# LightTable_Borders_CM_SP_ExternalMirror.net
KiCad netlist of a schematic drawn in EAGLE
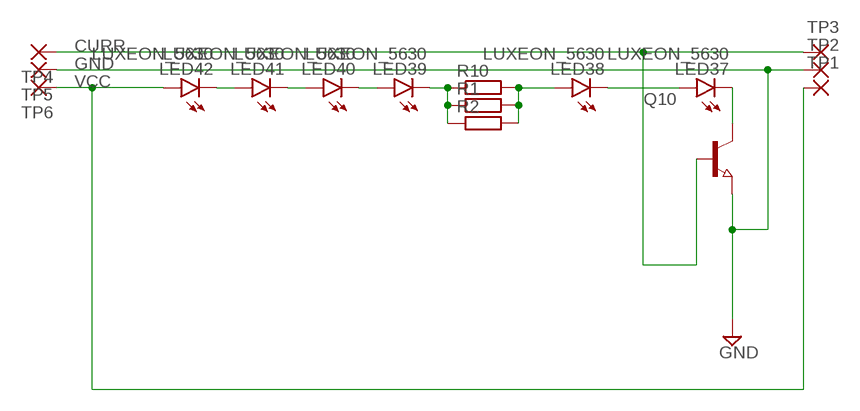
[diagram p0: schematic, sheet 1]

(export (version "E")
  (design (tool "Eeschema 10.0.6"))
  (components
    (comp (ref "LED37")
      (value "LUXEON_5630")
      (footprint "eagle-import:LUXEON_5630")
      (libsource (lib "eagle-import") (part "LUXEON_5630"))
    )
    (comp (ref "LED38")
      (value "LUXEON_5630")
      (footprint "eagle-import:LUXEON_5630")
      (libsource (lib "eagle-import") (part "LUXEON_5630"))
    )
    (comp (ref "LED39")
      (value "LUXEON_5630")
      (footprint "eagle-import:LUXEON_5630")
      (libsource (lib "eagle-import") (part "LUXEON_5630"))
    )
    (comp (ref "LED40")
      (value "LUXEON_5630")
      (footprint "eagle-import:LUXEON_5630")
      (libsource (lib "eagle-import") (part "LUXEON_5630"))
    )
    (comp (ref "LED41")
      (value "LUXEON_5630")
      (footprint "eagle-import:LUXEON_5630")
      (libsource (lib "eagle-import") (part "LUXEON_5630"))
    )
    (comp (ref "LED42")
      (value "LUXEON_5630")
      (footprint "eagle-import:LUXEON_5630")
      (libsource (lib "eagle-import") (part "LUXEON_5630"))
    )
    (comp (ref "Q10")
      (value "NPN-TRANSISTOR_SOT23")
      (footprint "eagle-import:SOT23")
      (libsource (lib "eagle-import") (part "NPN-TRANSISTOR_SOT23"))
    )
    (comp (ref "R1")
      (value "R-EU_R0805")
      (footprint "eagle-import:R0805")
      (libsource (lib "eagle-import") (part "R-EU_R0805"))
    )
    (comp (ref "R2")
      (value "R-EU_R0805")
      (footprint "eagle-import:R0805")
      (libsource (lib "eagle-import") (part "R-EU_R0805"))
    )
    (comp (ref "R10")
      (value "R-EU_R0805")
      (footprint "eagle-import:R0805")
      (libsource (lib "eagle-import") (part "R-EU_R0805"))
    )
    (comp (ref "TP1")
      (value "LSP10")
      (footprint "eagle-import:1,6_0,8")
      (libsource (lib "eagle-import") (part "1,6/0,8"))
    )
    (comp (ref "TP2")
      (value "LSP10")
      (footprint "eagle-import:1,6_0,8")
      (libsource (lib "eagle-import") (part "1,6/0,8"))
    )
    (comp (ref "TP3")
      (value "LSP10")
      (footprint "eagle-import:1,6_0,8")
      (libsource (lib "eagle-import") (part "1,6/0,8"))
    )
    (comp (ref "TP4")
      (value "LSP10")
      (footprint "eagle-import:1,6_0,8")
      (libsource (lib "eagle-import") (part "1,6/0,8"))
    )
    (comp (ref "TP5")
      (value "LSP10")
      (footprint "eagle-import:1,6_0,8")
      (libsource (lib "eagle-import") (part "1,6/0,8"))
    )
    (comp (ref "TP6")
      (value "LSP10")
      (footprint "eagle-import:1,6_0,8")
      (libsource (lib "eagle-import") (part "1,6/0,8"))
    )
  )
  (nets
    (net (code "1") (name "/CURR") (class "Default")
      (node (ref "Q10") (pin "1") (pinfunction "B_1") (pintype "passive"))
      (node (ref "TP3") (pin "1") (pinfunction "P_1") (pintype "passive"))
      (node (ref "TP4") (pin "1") (pinfunction "P_1") (pintype "passive"))
    )
    (net (code "2") (name "/VCC") (class "Default")
      (node (ref "LED42") (pin "2") (pinfunction "A_2") (pintype "passive"))
      (node (ref "TP1") (pin "1") (pinfunction "P_1") (pintype "passive"))
      (node (ref "TP6") (pin "1") (pinfunction "P_1") (pintype "passive"))
    )
    (net (code "3") (name "GND") (class "Default")
      (node (ref "Q10") (pin "2") (pinfunction "E_2") (pintype "passive"))
      (node (ref "TP2") (pin "1") (pinfunction "P_1") (pintype "passive"))
      (node (ref "TP5") (pin "1") (pinfunction "P_1") (pintype "passive"))
    )
    (net (code "4") (name "Net-(LED37-A)") (class "Default")
      (node (ref "LED37") (pin "2") (pinfunction "A_2") (pintype "passive"))
      (node (ref "LED38") (pin "1@1") (pinfunction "C_1@1") (pintype "passive"))
      (node (ref "LED38") (pin "1@2") (pinfunction "C_1@2") (pintype "passive"))
    )
    (net (code "5") (name "Net-(LED38-A)") (class "Default")
      (node (ref "LED38") (pin "2") (pinfunction "A_2") (pintype "passive"))
      (node (ref "R1") (pin "2") (pinfunction "2_2") (pintype "passive"))
      (node (ref "R10") (pin "2") (pinfunction "2_2") (pintype "passive"))
      (node (ref "R2") (pin "2") (pinfunction "2_2") (pintype "passive"))
    )
    (net (code "6") (name "Net-(LED39-A)") (class "Default")
      (node (ref "LED39") (pin "2") (pinfunction "A_2") (pintype "passive"))
      (node (ref "LED40") (pin "1@1") (pinfunction "C_1@1") (pintype "passive"))
      (node (ref "LED40") (pin "1@2") (pinfunction "C_1@2") (pintype "passive"))
    )
    (net (code "7") (name "Net-(LED39-C-Pad1@1)") (class "Default")
      (node (ref "LED39") (pin "1@1") (pinfunction "C_1@1") (pintype "passive"))
      (node (ref "LED39") (pin "1@2") (pinfunction "C_1@2") (pintype "passive"))
      (node (ref "R1") (pin "1") (pinfunction "1_1") (pintype "passive"))
      (node (ref "R10") (pin "1") (pinfunction "1_1") (pintype "passive"))
      (node (ref "R2") (pin "1") (pinfunction "1_1") (pintype "passive"))
    )
    (net (code "8") (name "Net-(LED40-A)") (class "Default")
      (node (ref "LED40") (pin "2") (pinfunction "A_2") (pintype "passive"))
      (node (ref "LED41") (pin "1@1") (pinfunction "C_1@1") (pintype "passive"))
      (node (ref "LED41") (pin "1@2") (pinfunction "C_1@2") (pintype "passive"))
    )
    (net (code "9") (name "Net-(LED41-A)") (class "Default")
      (node (ref "LED41") (pin "2") (pinfunction "A_2") (pintype "passive"))
      (node (ref "LED42") (pin "1@1") (pinfunction "C_1@1") (pintype "passive"))
      (node (ref "LED42") (pin "1@2") (pinfunction "C_1@2") (pintype "passive"))
    )
    (net (code "10") (name "Net-(Q10-C)") (class "Default")
      (node (ref "LED37") (pin "1@1") (pinfunction "C_1@1") (pintype "passive"))
      (node (ref "LED37") (pin "1@2") (pinfunction "C_1@2") (pintype "passive"))
      (node (ref "Q10") (pin "3") (pinfunction "C_3") (pintype "passive"))
    )
  )
)
